# stepper_driver1.net
KiCad netlist of a schematic drawn in EAGLE
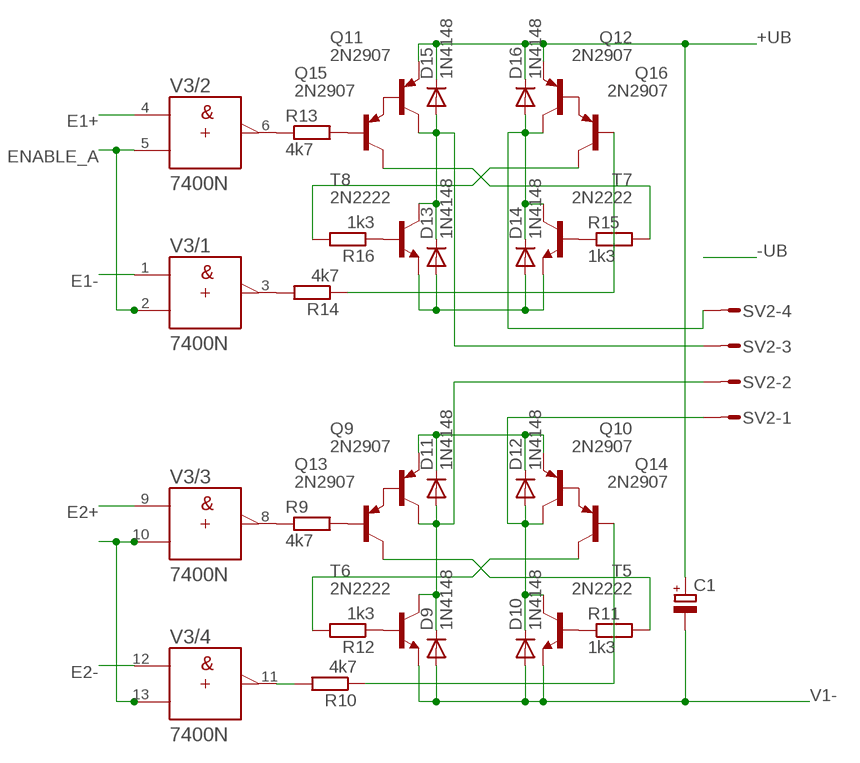
[diagram p0: schematic, sheet 1]

(export (version "E")
  (design (tool "Eeschema 10.0.6"))
  (components
    (comp (ref "C1")
      (value "CPOL-EUE3.5-10")
      (footprint "eagle-import:E3,5-10")
      (libsource (lib "eagle-import") (part "CPOL-EUE3.5-10"))
    )
    (comp (ref "D9")
      (value "1N4148")
      (footprint "eagle-import:D-2.5")
      (libsource (lib "eagle-import") (part "DIODE-D-2.5"))
    )
    (comp (ref "D10")
      (value "1N4148")
      (footprint "eagle-import:D-2.5")
      (libsource (lib "eagle-import") (part "DIODE-D-2.5"))
    )
    (comp (ref "D11")
      (value "1N4148")
      (footprint "eagle-import:D-2.5")
      (libsource (lib "eagle-import") (part "DIODE-D-2.5"))
    )
    (comp (ref "D12")
      (value "1N4148")
      (footprint "eagle-import:D-2.5")
      (libsource (lib "eagle-import") (part "DIODE-D-2.5"))
    )
    (comp (ref "D13")
      (value "1N4148")
      (footprint "eagle-import:D-2.5")
      (libsource (lib "eagle-import") (part "DIODE-D-2.5"))
    )
    (comp (ref "D14")
      (value "1N4148")
      (footprint "eagle-import:D-2.5")
      (libsource (lib "eagle-import") (part "DIODE-D-2.5"))
    )
    (comp (ref "D15")
      (value "1N4148")
      (footprint "eagle-import:D-2.5")
      (libsource (lib "eagle-import") (part "DIODE-D-2.5"))
    )
    (comp (ref "D16")
      (value "1N4148")
      (footprint "eagle-import:D-2.5")
      (libsource (lib "eagle-import") (part "DIODE-D-2.5"))
    )
    (comp (ref "Q9")
      (value "2N2907")
      (footprint "eagle-import:TO18")
      (libsource (lib "eagle-import") (part "2N2907"))
    )
    (comp (ref "Q10")
      (value "2N2907")
      (footprint "eagle-import:TO18")
      (libsource (lib "eagle-import") (part "2N2907"))
    )
    (comp (ref "Q11")
      (value "2N2907")
      (footprint "eagle-import:TO18")
      (libsource (lib "eagle-import") (part "2N2907"))
    )
    (comp (ref "Q12")
      (value "2N2907")
      (footprint "eagle-import:TO18")
      (libsource (lib "eagle-import") (part "2N2907"))
    )
    (comp (ref "Q13")
      (value "2N2907")
      (footprint "eagle-import:TO18")
      (libsource (lib "eagle-import") (part "2N2907"))
    )
    (comp (ref "Q14")
      (value "2N2907")
      (footprint "eagle-import:TO18")
      (libsource (lib "eagle-import") (part "2N2907"))
    )
    (comp (ref "Q15")
      (value "2N2907")
      (footprint "eagle-import:TO18")
      (libsource (lib "eagle-import") (part "2N2907"))
    )
    (comp (ref "Q16")
      (value "2N2907")
      (footprint "eagle-import:TO18")
      (libsource (lib "eagle-import") (part "2N2907"))
    )
    (comp (ref "R9")
      (value "4k7")
      (footprint "eagle-import:0207_10")
      (libsource (lib "eagle-import") (part "R-EU_0207/10"))
    )
    (comp (ref "R10")
      (value "4k7")
      (footprint "eagle-import:0207_12")
      (libsource (lib "eagle-import") (part "R-EU_0207/12"))
    )
    (comp (ref "R11")
      (value "1k3")
      (footprint "eagle-import:0207_10")
      (libsource (lib "eagle-import") (part "R-EU_0207/10"))
    )
    (comp (ref "R12")
      (value "1k3")
      (footprint "eagle-import:0207_10")
      (libsource (lib "eagle-import") (part "R-EU_0207/10"))
    )
    (comp (ref "R13")
      (value "4k7")
      (footprint "eagle-import:0207_10")
      (libsource (lib "eagle-import") (part "R-EU_0207/10"))
    )
    (comp (ref "R14")
      (value "4k7")
      (footprint "eagle-import:0207_10")
      (libsource (lib "eagle-import") (part "R-EU_0207/10"))
    )
    (comp (ref "R15")
      (value "1k3")
      (footprint "eagle-import:0207_10")
      (libsource (lib "eagle-import") (part "R-EU_0207/10"))
    )
    (comp (ref "R16")
      (value "1k3")
      (footprint "eagle-import:0207_10")
      (libsource (lib "eagle-import") (part "R-EU_0207/10"))
    )
    (comp (ref "SV2")
      (value "S04P")
      (footprint "eagle-import:S04P")
      (libsource (lib "eagle-import") (part "S04P"))
    )
    (comp (ref "T5")
      (value "2N2222")
      (footprint "eagle-import:TO18")
      (libsource (lib "eagle-import") (part "2N2222"))
    )
    (comp (ref "T6")
      (value "2N2222")
      (footprint "eagle-import:TO18")
      (libsource (lib "eagle-import") (part "2N2222"))
    )
    (comp (ref "T7")
      (value "2N2222")
      (footprint "eagle-import:TO18")
      (libsource (lib "eagle-import") (part "2N2222"))
    )
    (comp (ref "T8")
      (value "2N2222")
      (footprint "eagle-import:TO18")
      (libsource (lib "eagle-import") (part "2N2222"))
    )
    (comp (ref "V3")
      (value "7400N")
      (footprint "eagle-import:DIL14")
      (libsource (lib "eagle-import") (part "7400N"))
    )
  )
  (nets
    (net (code "1") (name "/+UB") (class "Default")
      (node (ref "C1") (pin "+") (pinfunction "+_+") (pintype "passive"))
      (node (ref "D11") (pin "C") (pinfunction "C_C") (pintype "passive"))
      (node (ref "D12") (pin "C") (pinfunction "C_C") (pintype "passive"))
      (node (ref "D15") (pin "C") (pinfunction "C_C") (pintype "passive"))
      (node (ref "D16") (pin "C") (pinfunction "C_C") (pintype "passive"))
      (node (ref "Q10") (pin "1") (pinfunction "E_1") (pintype "passive"))
      (node (ref "Q11") (pin "1") (pinfunction "E_1") (pintype "passive"))
      (node (ref "Q12") (pin "1") (pinfunction "E_1") (pintype "passive"))
      (node (ref "Q9") (pin "1") (pinfunction "E_1") (pintype "passive"))
    )
    (net (code "3") (name "/E1+") (class "Default")
      (node (ref "V3") (pin "4") (pinfunction "A_4") (pintype "input"))
    )
    (net (code "4") (name "/E1-") (class "Default")
      (node (ref "V3") (pin "1") (pinfunction "A_1") (pintype "input"))
    )
    (net (code "5") (name "/E2+") (class "Default")
      (node (ref "V3") (pin "9") (pinfunction "A_9") (pintype "input"))
    )
    (net (code "6") (name "/E2-") (class "Default")
      (node (ref "V3") (pin "12") (pinfunction "A_12") (pintype "input"))
    )
    (net (code "7") (name "/ENABLE_A") (class "Default")
      (node (ref "V3") (pin "2") (pinfunction "B_2") (pintype "input"))
      (node (ref "V3") (pin "5") (pinfunction "B_5") (pintype "input"))
    )
    (net (code "8") (name "/V1-") (class "Default")
      (node (ref "C1") (pin "-") (pinfunction "-_-") (pintype "passive"))
      (node (ref "D10") (pin "A") (pinfunction "A_A") (pintype "passive"))
      (node (ref "D13") (pin "A") (pinfunction "A_A") (pintype "passive"))
      (node (ref "D14") (pin "A") (pinfunction "A_A") (pintype "passive"))
      (node (ref "D9") (pin "A") (pinfunction "A_A") (pintype "passive"))
      (node (ref "T5") (pin "1") (pinfunction "E_1") (pintype "passive"))
      (node (ref "T6") (pin "1") (pinfunction "E_1") (pintype "passive"))
      (node (ref "T7") (pin "1") (pinfunction "E_1") (pintype "passive"))
      (node (ref "T8") (pin "1") (pinfunction "E_1") (pintype "passive"))
    )
    (net (code "9") (name "Net-(Q9-C)") (class "Default")
      (node (ref "D11") (pin "A") (pinfunction "A_A") (pintype "passive"))
      (node (ref "D9") (pin "C") (pinfunction "C_C") (pintype "passive"))
      (node (ref "Q9") (pin "3") (pinfunction "C_3") (pintype "passive"))
      (node (ref "SV2") (pin "2") (pinfunction "S_2") (pintype "passive"))
      (node (ref "T6") (pin "3") (pinfunction "C_3") (pintype "passive"))
    )
    (net (code "10") (name "Net-(Q10-B)") (class "Default")
      (node (ref "Q10") (pin "2") (pinfunction "B_2") (pintype "passive"))
      (node (ref "Q14") (pin "1") (pinfunction "E_1") (pintype "passive"))
    )
    (net (code "11") (name "Net-(Q10-C)") (class "Default")
      (node (ref "D10") (pin "C") (pinfunction "C_C") (pintype "passive"))
      (node (ref "D12") (pin "A") (pinfunction "A_A") (pintype "passive"))
      (node (ref "Q10") (pin "3") (pinfunction "C_3") (pintype "passive"))
      (node (ref "SV2") (pin "1") (pinfunction "S_1") (pintype "passive"))
      (node (ref "T5") (pin "3") (pinfunction "C_3") (pintype "passive"))
    )
    (net (code "12") (name "Net-(Q11-B)") (class "Default")
      (node (ref "Q11") (pin "2") (pinfunction "B_2") (pintype "passive"))
      (node (ref "Q15") (pin "1") (pinfunction "E_1") (pintype "passive"))
    )
    (net (code "13") (name "Net-(Q11-C)") (class "Default")
      (node (ref "D13") (pin "C") (pinfunction "C_C") (pintype "passive"))
      (node (ref "D15") (pin "A") (pinfunction "A_A") (pintype "passive"))
      (node (ref "Q11") (pin "3") (pinfunction "C_3") (pintype "passive"))
      (node (ref "SV2") (pin "3") (pinfunction "S_3") (pintype "passive"))
      (node (ref "T8") (pin "3") (pinfunction "C_3") (pintype "passive"))
    )
    (net (code "14") (name "Net-(Q12-B)") (class "Default")
      (node (ref "Q12") (pin "2") (pinfunction "B_2") (pintype "passive"))
      (node (ref "Q16") (pin "1") (pinfunction "E_1") (pintype "passive"))
    )
    (net (code "15") (name "Net-(Q12-C)") (class "Default")
      (node (ref "D14") (pin "C") (pinfunction "C_C") (pintype "passive"))
      (node (ref "D16") (pin "A") (pinfunction "A_A") (pintype "passive"))
      (node (ref "Q12") (pin "3") (pinfunction "C_3") (pintype "passive"))
      (node (ref "SV2") (pin "4") (pinfunction "S_4") (pintype "passive"))
      (node (ref "T7") (pin "3") (pinfunction "C_3") (pintype "passive"))
    )
    (net (code "16") (name "Net-(Q13-B)") (class "Default")
      (node (ref "Q13") (pin "2") (pinfunction "B_2") (pintype "passive"))
      (node (ref "R9") (pin "2") (pinfunction "2_2") (pintype "passive"))
    )
    (net (code "17") (name "Net-(Q13-C)") (class "Default")
      (node (ref "Q13") (pin "3") (pinfunction "C_3") (pintype "passive"))
      (node (ref "R11") (pin "2") (pinfunction "2_2") (pintype "passive"))
    )
    (net (code "18") (name "Net-(Q13-E)") (class "Default")
      (node (ref "Q13") (pin "1") (pinfunction "E_1") (pintype "passive"))
      (node (ref "Q9") (pin "2") (pinfunction "B_2") (pintype "passive"))
    )
    (net (code "19") (name "Net-(Q14-B)") (class "Default")
      (node (ref "Q14") (pin "2") (pinfunction "B_2") (pintype "passive"))
      (node (ref "R10") (pin "1") (pinfunction "1_1") (pintype "passive"))
    )
    (net (code "20") (name "Net-(Q14-C)") (class "Default")
      (node (ref "Q14") (pin "3") (pinfunction "C_3") (pintype "passive"))
      (node (ref "R12") (pin "2") (pinfunction "2_2") (pintype "passive"))
    )
    (net (code "21") (name "Net-(Q15-B)") (class "Default")
      (node (ref "Q15") (pin "2") (pinfunction "B_2") (pintype "passive"))
      (node (ref "R13") (pin "2") (pinfunction "2_2") (pintype "passive"))
    )
    (net (code "22") (name "Net-(Q15-C)") (class "Default")
      (node (ref "Q15") (pin "3") (pinfunction "C_3") (pintype "passive"))
      (node (ref "R15") (pin "2") (pinfunction "2_2") (pintype "passive"))
    )
    (net (code "23") (name "Net-(Q16-B)") (class "Default")
      (node (ref "Q16") (pin "2") (pinfunction "B_2") (pintype "passive"))
      (node (ref "R14") (pin "1") (pinfunction "1_1") (pintype "passive"))
    )
    (net (code "24") (name "Net-(Q16-C)") (class "Default")
      (node (ref "Q16") (pin "3") (pinfunction "C_3") (pintype "passive"))
      (node (ref "R16") (pin "2") (pinfunction "2_2") (pintype "passive"))
    )
    (net (code "25") (name "Net-(T5-B)") (class "Default")
      (node (ref "R11") (pin "1") (pinfunction "1_1") (pintype "passive"))
      (node (ref "T5") (pin "2") (pinfunction "B_2") (pintype "passive"))
    )
    (net (code "26") (name "Net-(T6-B)") (class "Default")
      (node (ref "R12") (pin "1") (pinfunction "1_1") (pintype "passive"))
      (node (ref "T6") (pin "2") (pinfunction "B_2") (pintype "passive"))
    )
    (net (code "27") (name "Net-(T7-B)") (class "Default")
      (node (ref "R15") (pin "1") (pinfunction "1_1") (pintype "passive"))
      (node (ref "T7") (pin "2") (pinfunction "B_2") (pintype "passive"))
    )
    (net (code "28") (name "Net-(T8-B)") (class "Default")
      (node (ref "R16") (pin "1") (pinfunction "1_1") (pintype "passive"))
      (node (ref "T8") (pin "2") (pinfunction "B_2") (pintype "passive"))
    )
    (net (code "29") (name "Net-(V3C-Y)") (class "Default")
      (node (ref "R14") (pin "2") (pinfunction "2_2") (pintype "passive"))
      (node (ref "V3") (pin "3") (pinfunction "Y_3") (pintype "output"))
    )
    (net (code "30") (name "Net-(V3D-Y)") (class "Default")
      (node (ref "R13") (pin "1") (pinfunction "1_1") (pintype "passive"))
      (node (ref "V3") (pin "6") (pinfunction "Y_6") (pintype "output"))
    )
    (net (code "31") (name "Net-(V3E-B)") (class "Default")
      (node (ref "V3") (pin "10") (pinfunction "B_10") (pintype "input"))
      (node (ref "V3") (pin "13") (pinfunction "B_13") (pintype "input"))
    )
    (net (code "32") (name "Net-(V3E-Y)") (class "Default")
      (node (ref "R9") (pin "1") (pinfunction "1_1") (pintype "passive"))
      (node (ref "V3") (pin "8") (pinfunction "Y_8") (pintype "output"))
    )
    (net (code "33") (name "Net-(V3F-Y)") (class "Default")
      (node (ref "R10") (pin "2") (pinfunction "2_2") (pintype "passive"))
      (node (ref "V3") (pin "11") (pinfunction "Y_11") (pintype "output"))
    )
  )
)
